# RPI_3.net
KiCad netlist of a schematic drawn in Altium Designer
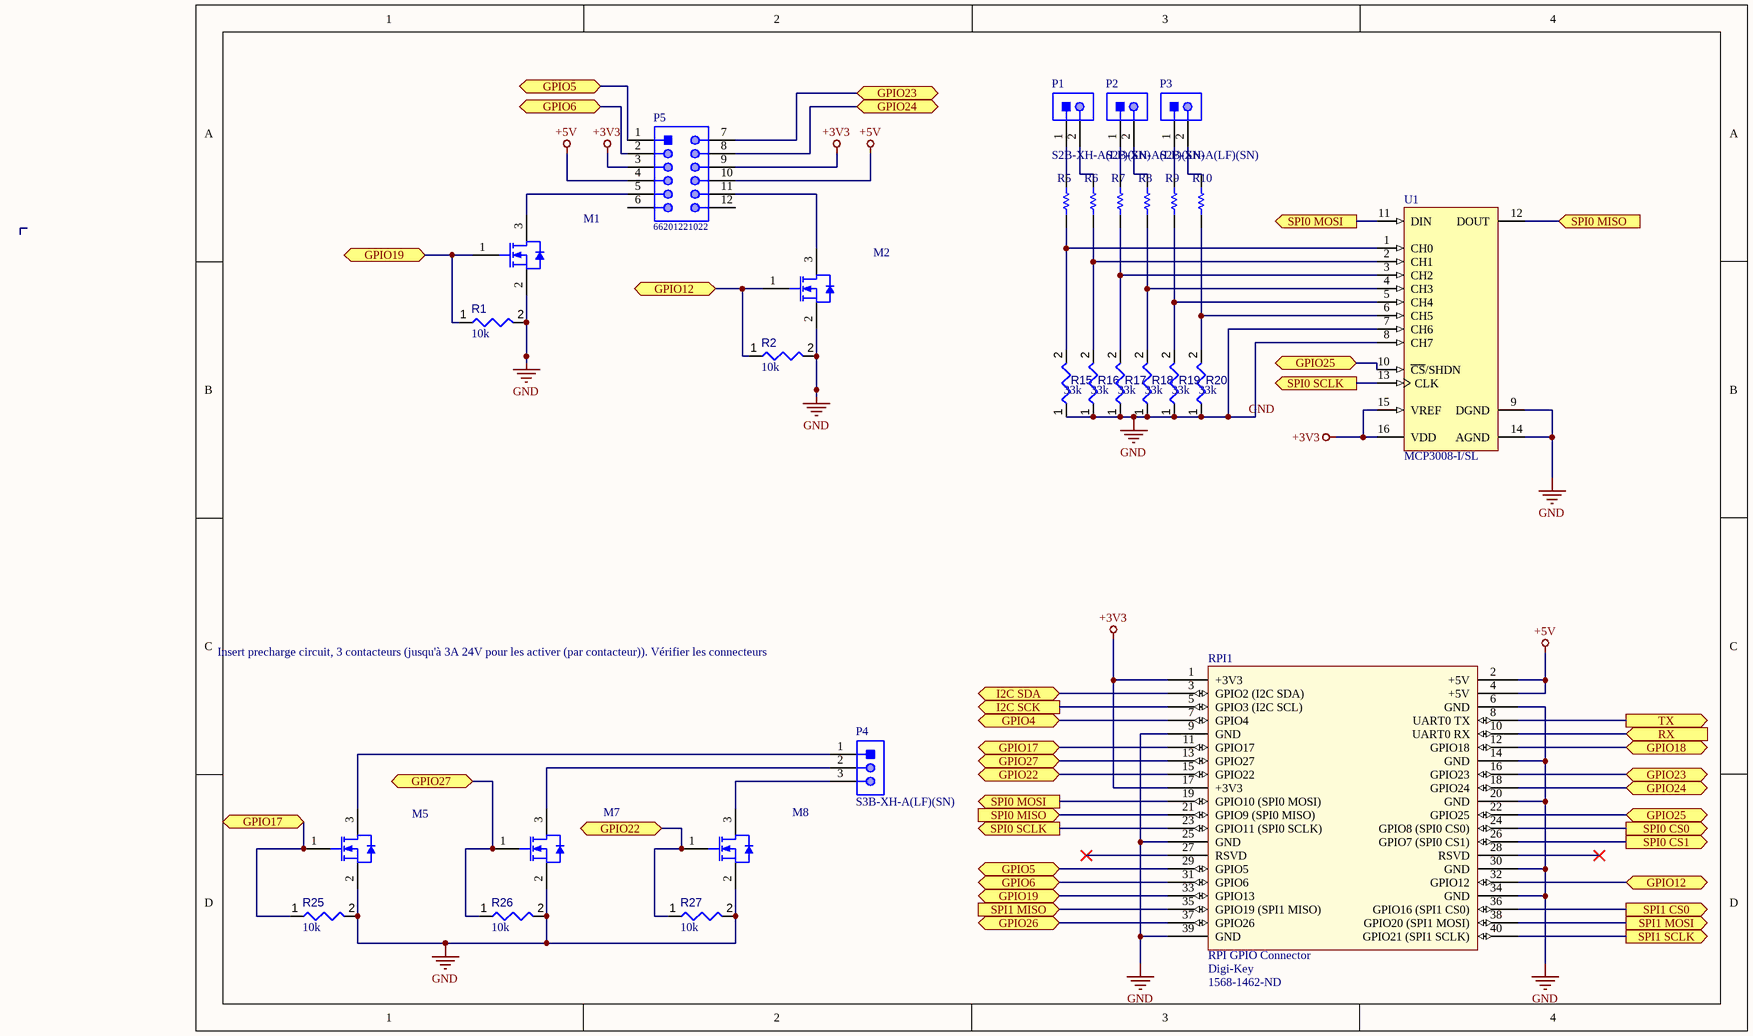
[diagram p0: RPI 3.SchDoc]

(export (version "E")
  (design (tool "Eeschema 10.0.6"))
  (components
    (comp (ref "M1")
      (value "BSS138")
      (footprint "FAIR-SOT23-3_V")
      (fields (field (name "MANUFACTURER") "Fairchild") (field (name "POWER") "360mW"))
      (libsource (lib "École Polytechnique de Montréal") (part "NEMOS-GSD-3"))
    )
    (comp (ref "M2")
      (value "BSS138")
      (footprint "FAIR-SOT23-3_V")
      (fields (field (name "MANUFACTURER") "Fairchild") (field (name "POWER") "360mW"))
      (libsource (lib "École Polytechnique de Montréal") (part "NEMOS-GSD-3"))
    )
    (comp (ref "M5")
      (value "BSS138")
      (footprint "FAIR-SOT23-3_V")
      (fields (field (name "MANUFACTURER") "Fairchild") (field (name "POWER") "360mW"))
      (libsource (lib "École Polytechnique de Montréal") (part "NEMOS-GSD-3"))
    )
    (comp (ref "M7")
      (value "BSS138")
      (footprint "FAIR-SOT23-3_V")
      (fields (field (name "MANUFACTURER") "Fairchild") (field (name "POWER") "360mW"))
      (libsource (lib "École Polytechnique de Montréal") (part "NEMOS-GSD-3"))
    )
    (comp (ref "M8")
      (value "BSS138")
      (footprint "FAIR-SOT23-3_V")
      (fields (field (name "MANUFACTURER") "Fairchild") (field (name "POWER") "360mW"))
      (libsource (lib "École Polytechnique de Montréal") (part "NEMOS-GSD-3"))
    )
    (comp (ref "P1")
      (value "S2B-XH-A(LF)(SN)")
      (footprint "JST-S2B-XH-A(LF)(SN)_V")
      (fields (field (name "MANUFACTURER") "JST"))
      (libsource (lib "École Polytechnique de Montréal") (part "CN-1P-M-R2"))
    )
    (comp (ref "P2")
      (value "S2B-XH-A(LF)(SN)")
      (footprint "JST-S2B-XH-A(LF)(SN)_V")
      (fields (field (name "MANUFACTURER") "JST"))
      (libsource (lib "École Polytechnique de Montréal") (part "CN-1P-M-R2"))
    )
    (comp (ref "P3")
      (value "S2B-XH-A(LF)(SN)")
      (footprint "JST-S2B-XH-A(LF)(SN)_V")
      (fields (field (name "MANUFACTURER") "JST"))
      (libsource (lib "École Polytechnique de Montréal") (part "CN-1P-M-R2"))
    )
    (comp (ref "P4")
      (value "S3B-XH-A(LF)(SN)")
      (footprint "JST-S3B-XH-A(LF)(SN)_V")
      (fields (field (name "MANUFACTURER") "JST"))
      (libsource (lib "École Polytechnique de Montréal") (part "CN-1P-M-R3"))
    )
    (comp (ref "P5")
      (value "66201221022")
      (footprint "66201221022")
      (description "THT Male Header WR-MPC3, with Snap-in Plastic Pegs, Right Angled, Dual Row, pitch 3 mm, 12 pins")
      (libsource (lib "École Polytechnique de Montréal") (part "WE-CN-2P-M-R12_A"))
    )
    (comp (ref "R1")
      (value "10k")
      (footprint "RESC0402(1005)_L")
      (description "Chip Resistor, 10 kOhms, +/-1 %, 63 mW, -55 to 125 degC, 0402")
      (fields (field (name "POWER") "63mW") (field (name "TOLERANCE") "1%"))
      (libsource (lib "École Polytechnique de Montréal") (part "RES-2"))
    )
    (comp (ref "R2")
      (value "10k")
      (footprint "RESC0402(1005)_L")
      (description "Chip Resistor, 10 kOhms, +/-1 %, 63 mW, -55 to 125 degC, 0402")
      (fields (field (name "POWER") "63mW") (field (name "TOLERANCE") "1%"))
      (libsource (lib "École Polytechnique de Montréal") (part "RES-2"))
    )
    (comp (ref "R5")
      (value "RES")
      (footprint "RESC1005X40X25LL05T10")
      (description "Res General Purpose Thick Film 0402 18k Ohm 5% 1/16W ±100ppm/°C Molded Paper T/R")
      (libsource (lib "École Polytechnique de Montréal") (part "RES"))
    )
    (comp (ref "R6")
      (value "RES")
      (footprint "RESC1005X40X25LL05T10")
      (description "Res General Purpose Thick Film 0402 18k Ohm 5% 1/16W ±100ppm/°C Molded Paper T/R")
      (libsource (lib "École Polytechnique de Montréal") (part "RES"))
    )
    (comp (ref "R7")
      (value "RES")
      (footprint "RESC1005X40X25LL05T10")
      (description "Res General Purpose Thick Film 0402 18k Ohm 5% 1/16W ±100ppm/°C Molded Paper T/R")
      (libsource (lib "École Polytechnique de Montréal") (part "RES"))
    )
    (comp (ref "R8")
      (value "RES")
      (footprint "RESC1005X40X25LL05T10")
      (description "Res General Purpose Thick Film 0402 18k Ohm 5% 1/16W ±100ppm/°C Molded Paper T/R")
      (libsource (lib "École Polytechnique de Montréal") (part "RES"))
    )
    (comp (ref "R9")
      (value "RES")
      (footprint "RESC1005X40X25LL05T10")
      (description "Res General Purpose Thick Film 0402 18k Ohm 5% 1/16W ±100ppm/°C Molded Paper T/R")
      (libsource (lib "École Polytechnique de Montréal") (part "RES"))
    )
    (comp (ref "R10")
      (value "RES")
      (footprint "RESC1005X40X25LL05T10")
      (description "Res General Purpose Thick Film 0402 18k Ohm 5% 1/16W ±100ppm/°C Molded Paper T/R")
      (libsource (lib "École Polytechnique de Montréal") (part "RES"))
    )
    (comp (ref "R15")
      (value "33k")
      (footprint "RESC1005X40X25ML10T10")
      (description "Chip Resistor, 33 KOhm, +/- 5%, 0.063 W, -55 to 155 degC, 0402 (1005 Metric)")
      (fields (field (name "TOLERANCE") "5%") (field (name "POWER") "63mW"))
      (libsource (lib "École Polytechnique de Montréal") (part "RES-2"))
    )
    (comp (ref "R16")
      (value "33k")
      (footprint "RESC1005X40X25ML10T10")
      (description "Chip Resistor, 33 KOhm, +/- 5%, 0.063 W, -55 to 155 degC, 0402 (1005 Metric)")
      (fields (field (name "TOLERANCE") "5%") (field (name "POWER") "63mW"))
      (libsource (lib "École Polytechnique de Montréal") (part "RES-2"))
    )
    (comp (ref "R17")
      (value "33k")
      (footprint "RESC1005X40X25ML10T10")
      (description "Chip Resistor, 33 KOhm, +/- 5%, 0.063 W, -55 to 155 degC, 0402 (1005 Metric)")
      (fields (field (name "TOLERANCE") "5%") (field (name "POWER") "63mW"))
      (libsource (lib "École Polytechnique de Montréal") (part "RES-2"))
    )
    (comp (ref "R18")
      (value "33k")
      (footprint "RESC1005X40X25ML10T10")
      (description "Chip Resistor, 33 KOhm, +/- 5%, 0.063 W, -55 to 155 degC, 0402 (1005 Metric)")
      (fields (field (name "TOLERANCE") "5%") (field (name "POWER") "63mW"))
      (libsource (lib "École Polytechnique de Montréal") (part "RES-2"))
    )
    (comp (ref "R19")
      (value "33k")
      (footprint "RESC1005X40X25ML10T10")
      (description "Chip Resistor, 33 KOhm, +/- 5%, 0.063 W, -55 to 155 degC, 0402 (1005 Metric)")
      (fields (field (name "TOLERANCE") "5%") (field (name "POWER") "63mW"))
      (libsource (lib "École Polytechnique de Montréal") (part "RES-2"))
    )
    (comp (ref "R20")
      (value "33k")
      (footprint "RESC1005X40X25ML10T10")
      (description "Chip Resistor, 33 KOhm, +/- 5%, 0.063 W, -55 to 155 degC, 0402 (1005 Metric)")
      (fields (field (name "TOLERANCE") "5%") (field (name "POWER") "63mW"))
      (libsource (lib "École Polytechnique de Montréal") (part "RES-2"))
    )
    (comp (ref "R25")
      (value "10k")
      (footprint "RESC0402(1005)_L")
      (description "Chip Resistor, 10 kOhms, +/-1 %, 63 mW, -55 to 125 degC, 0402")
      (fields (field (name "POWER") "63mW") (field (name "TOLERANCE") "1%"))
      (libsource (lib "École Polytechnique de Montréal") (part "RES-2"))
    )
    (comp (ref "R26")
      (value "10k")
      (footprint "RESC0402(1005)_L")
      (description "Chip Resistor, 10 kOhms, +/-1 %, 63 mW, -55 to 125 degC, 0402")
      (fields (field (name "POWER") "63mW") (field (name "TOLERANCE") "1%"))
      (libsource (lib "École Polytechnique de Montréal") (part "RES-2"))
    )
    (comp (ref "R27")
      (value "10k")
      (footprint "RESC0402(1005)_L")
      (description "Chip Resistor, 10 kOhms, +/-1 %, 63 mW, -55 to 125 degC, 0402")
      (fields (field (name "POWER") "63mW") (field (name "TOLERANCE") "1%"))
      (libsource (lib "École Polytechnique de Montréal") (part "RES-2"))
    )
    (comp (ref "RPI1")
      (value "RPI GPIO Connector")
      (footprint "rpi")
      (description "GPIO Header for Raspberry Pi A+/B+/Pi 2/Pi 3 - 2x20")
      (fields
        (field (name "MANUFACTURER") "SparkFun Electronics")
        (field (name "MANUFACTURER PART NUMBER") "PRT-14017")
        (field (name "SUPPLIER 1") "Digi-Key")
        (field (name "SUPPLIER PART NUMBER 1") "1568-1462-ND")
      )
      (libsource (lib "rpi") (part "rpi connector"))
    )
    (comp (ref "U1")
      (value "MCP3008-I/SL")
      (footprint "SOIC-SL16_L")
      (libsource (lib "Altium Content Vault") (part "CON-ADC-MCP3008-16"))
    )
  )
  (nets
    (net (code "1") (name "+3V3") (class "Default")
      (node (ref "P5") (pin "3") (pinfunction "3_3") (pintype "passive"))
      (node (ref "P5") (pin "9") (pinfunction "9_9") (pintype "passive"))
      (node (ref "RPI1") (pin "1") (pinfunction "+3V3_1") (pintype "power_in"))
      (node (ref "RPI1") (pin "17") (pinfunction "+3V3_17") (pintype "power_in"))
      (node (ref "U1") (pin "15") (pinfunction "VREF_15") (pintype "input"))
      (node (ref "U1") (pin "16") (pinfunction "VDD_16") (pintype "power_in"))
    )
    (net (code "2") (name "+5V") (class "Default")
      (node (ref "P5") (pin "10") (pinfunction "10_10") (pintype "passive"))
      (node (ref "P5") (pin "4") (pinfunction "4_4") (pintype "passive"))
      (node (ref "RPI1") (pin "2") (pinfunction "+5V_2") (pintype "power_in"))
      (node (ref "RPI1") (pin "4") (pinfunction "+5V_4") (pintype "power_in"))
    )
    (net (code "3") (name "/GPIO4") (class "Default")
      (node (ref "RPI1") (pin "7") (pinfunction "GPIO4_7") (pintype "bidirectional"))
    )
    (net (code "4") (name "/GPIO5") (class "Default")
      (node (ref "P5") (pin "1") (pinfunction "1_1") (pintype "passive"))
      (node (ref "RPI1") (pin "29") (pinfunction "GPIO5_29") (pintype "bidirectional"))
    )
    (net (code "5") (name "/GPIO6") (class "Default")
      (node (ref "P5") (pin "2") (pinfunction "2_2") (pintype "passive"))
      (node (ref "RPI1") (pin "31") (pinfunction "GPIO6_31") (pintype "bidirectional"))
    )
    (net (code "6") (name "/GPIO12") (class "Default")
      (node (ref "M2") (pin "1") (pinfunction "G_1") (pintype "passive"))
      (node (ref "R2") (pin "1") (pinfunction "1_1") (pintype "passive"))
      (node (ref "RPI1") (pin "32") (pinfunction "GPIO12_32") (pintype "bidirectional"))
    )
    (net (code "7") (name "/GPIO17") (class "Default")
      (node (ref "M5") (pin "1") (pinfunction "G_1") (pintype "passive"))
      (node (ref "R25") (pin "1") (pinfunction "1_1") (pintype "passive"))
      (node (ref "RPI1") (pin "11") (pinfunction "GPIO17_11") (pintype "bidirectional"))
    )
    (net (code "8") (name "/GPIO18") (class "Default")
      (node (ref "RPI1") (pin "12") (pinfunction "GPIO18_12") (pintype "bidirectional"))
    )
    (net (code "9") (name "/GPIO19") (class "Default")
      (node (ref "M1") (pin "1") (pinfunction "G_1") (pintype "passive"))
      (node (ref "R1") (pin "1") (pinfunction "1_1") (pintype "passive"))
      (node (ref "RPI1") (pin "33") (pinfunction "GPIO13_33") (pintype "bidirectional"))
    )
    (net (code "10") (name "/GPIO22") (class "Default")
      (node (ref "M8") (pin "1") (pinfunction "G_1") (pintype "passive"))
      (node (ref "R27") (pin "1") (pinfunction "1_1") (pintype "passive"))
      (node (ref "RPI1") (pin "15") (pinfunction "GPIO22_15") (pintype "bidirectional"))
    )
    (net (code "11") (name "/GPIO23") (class "Default")
      (node (ref "P5") (pin "7") (pinfunction "7_7") (pintype "passive"))
      (node (ref "RPI1") (pin "16") (pinfunction "GPIO23_16") (pintype "bidirectional"))
    )
    (net (code "12") (name "/GPIO24") (class "Default")
      (node (ref "P5") (pin "8") (pinfunction "8_8") (pintype "passive"))
      (node (ref "RPI1") (pin "18") (pinfunction "GPIO24_18") (pintype "bidirectional"))
    )
    (net (code "13") (name "/GPIO25") (class "Default")
      (node (ref "RPI1") (pin "22") (pinfunction "GPIO25_22") (pintype "bidirectional"))
      (node (ref "U1") (pin "10") (pinfunction "~{CS}/SHDN_10") (pintype "input"))
    )
    (net (code "14") (name "/GPIO26") (class "Default")
      (node (ref "RPI1") (pin "37") (pinfunction "GPIO26_37") (pintype "bidirectional"))
    )
    (net (code "15") (name "/GPIO27") (class "Default")
      (node (ref "M7") (pin "1") (pinfunction "G_1") (pintype "passive"))
      (node (ref "R26") (pin "1") (pinfunction "1_1") (pintype "passive"))
      (node (ref "RPI1") (pin "13") (pinfunction "GPIO27_13") (pintype "bidirectional"))
    )
    (net (code "16") (name "/I2C SCK") (class "Default")
      (node (ref "RPI1") (pin "5") (pinfunction "GPIO3_(I2C_SCL)_5") (pintype "bidirectional"))
    )
    (net (code "17") (name "/I2C SDA") (class "Default")
      (node (ref "RPI1") (pin "3") (pinfunction "GPIO2_(I2C_SDA)_3") (pintype "bidirectional"))
    )
    (net (code "18") (name "/RX") (class "Default")
      (node (ref "RPI1") (pin "10") (pinfunction "UART0_RX_10") (pintype "bidirectional"))
    )
    (net (code "19") (name "/SPI0 CS0") (class "Default")
      (node (ref "RPI1") (pin "24") (pinfunction "GPIO8_(SPI0_CS0)_24") (pintype "bidirectional"))
    )
    (net (code "20") (name "/SPI0 CS1") (class "Default")
      (node (ref "RPI1") (pin "26") (pinfunction "GPIO7_(SPI0_CS1)_26") (pintype "bidirectional"))
    )
    (net (code "21") (name "/SPI0 MISO") (class "Default")
      (node (ref "RPI1") (pin "21") (pinfunction "GPIO9_(SPI0_MISO)_21") (pintype "bidirectional"))
      (node (ref "U1") (pin "12") (pinfunction "DOUT_12") (pintype "tri_state"))
    )
    (net (code "22") (name "/SPI0 MOSI") (class "Default")
      (node (ref "RPI1") (pin "19") (pinfunction "GPIO10_(SPI0_MOSI)_19") (pintype "bidirectional"))
      (node (ref "U1") (pin "11") (pinfunction "DIN_11") (pintype "input"))
    )
    (net (code "23") (name "/SPI0 SCLK") (class "Default")
      (node (ref "RPI1") (pin "23") (pinfunction "GPIO11_(SPI0_SCLK)_23") (pintype "bidirectional"))
      (node (ref "U1") (pin "13") (pinfunction "CLK_13") (pintype "input"))
    )
    (net (code "24") (name "/SPI1 CS0") (class "Default")
      (node (ref "RPI1") (pin "36") (pinfunction "GPIO16_(SPI1_CS0)_36") (pintype "bidirectional"))
    )
    (net (code "25") (name "/SPI1 MISO") (class "Default")
      (node (ref "RPI1") (pin "35") (pinfunction "GPIO19_(SPI1_MISO)_35") (pintype "bidirectional"))
    )
    (net (code "26") (name "/SPI1 MOSI") (class "Default")
      (node (ref "RPI1") (pin "38") (pinfunction "GPIO20_(SPI1_MOSI)_38") (pintype "bidirectional"))
    )
    (net (code "27") (name "/SPI1 SCLK") (class "Default")
      (node (ref "RPI1") (pin "40") (pinfunction "GPIO21_(SPI1_SCLK)_40") (pintype "bidirectional"))
    )
    (net (code "28") (name "/TX") (class "Default")
      (node (ref "RPI1") (pin "8") (pinfunction "UART0_TX_8") (pintype "bidirectional"))
    )
    (net (code "29") (name "GND") (class "Default")
      (node (ref "M1") (pin "2") (pinfunction "S_2") (pintype "passive"))
      (node (ref "M2") (pin "2") (pinfunction "S_2") (pintype "passive"))
      (node (ref "M5") (pin "2") (pinfunction "S_2") (pintype "passive"))
      (node (ref "M7") (pin "2") (pinfunction "S_2") (pintype "passive"))
      (node (ref "M8") (pin "2") (pinfunction "S_2") (pintype "passive"))
      (node (ref "R1") (pin "2") (pinfunction "2_2") (pintype "passive"))
      (node (ref "R15") (pin "1") (pinfunction "1_1") (pintype "passive"))
      (node (ref "R16") (pin "1") (pinfunction "1_1") (pintype "passive"))
      (node (ref "R17") (pin "1") (pinfunction "1_1") (pintype "passive"))
      (node (ref "R18") (pin "1") (pinfunction "1_1") (pintype "passive"))
      (node (ref "R19") (pin "1") (pinfunction "1_1") (pintype "passive"))
      (node (ref "R2") (pin "2") (pinfunction "2_2") (pintype "passive"))
      (node (ref "R20") (pin "1") (pinfunction "1_1") (pintype "passive"))
      (node (ref "R25") (pin "2") (pinfunction "2_2") (pintype "passive"))
      (node (ref "R26") (pin "2") (pinfunction "2_2") (pintype "passive"))
      (node (ref "R27") (pin "2") (pinfunction "2_2") (pintype "passive"))
      (node (ref "RPI1") (pin "14") (pinfunction "GND_14") (pintype "power_in"))
      (node (ref "RPI1") (pin "20") (pinfunction "GND_20") (pintype "power_in"))
      (node (ref "RPI1") (pin "25") (pinfunction "GND_25") (pintype "power_in"))
      (node (ref "RPI1") (pin "30") (pinfunction "GND_30") (pintype "power_in"))
      (node (ref "RPI1") (pin "34") (pinfunction "GND_34") (pintype "passive"))
      (node (ref "RPI1") (pin "39") (pinfunction "GND_39") (pintype "power_in"))
      (node (ref "RPI1") (pin "6") (pinfunction "GND_6") (pintype "power_in"))
      (node (ref "RPI1") (pin "9") (pinfunction "GND_9") (pintype "power_in"))
      (node (ref "U1") (pin "14") (pinfunction "AGND_14") (pintype "power_in"))
      (node (ref "U1") (pin "7") (pinfunction "CH6_7") (pintype "input"))
      (node (ref "U1") (pin "8") (pinfunction "CH7_8") (pintype "input"))
      (node (ref "U1") (pin "9") (pinfunction "DGND_9") (pintype "power_in"))
    )
    (net (code "30") (name "Net-(M1-D)") (class "Default")
      (node (ref "M1") (pin "3") (pinfunction "D_3") (pintype "passive"))
      (node (ref "P5") (pin "5") (pinfunction "5_5") (pintype "passive"))
    )
    (net (code "31") (name "Net-(M2-D)") (class "Default")
      (node (ref "M2") (pin "3") (pinfunction "D_3") (pintype "passive"))
      (node (ref "P5") (pin "11") (pinfunction "11_11") (pintype "passive"))
    )
    (net (code "32") (name "Net-(M5-D)") (class "Default")
      (node (ref "M5") (pin "3") (pinfunction "D_3") (pintype "passive"))
      (node (ref "P4") (pin "1") (pinfunction "1_1") (pintype "passive"))
    )
    (net (code "33") (name "Net-(M7-D)") (class "Default")
      (node (ref "M7") (pin "3") (pinfunction "D_3") (pintype "passive"))
      (node (ref "P4") (pin "2") (pinfunction "2_2") (pintype "passive"))
    )
    (net (code "34") (name "Net-(M8-D)") (class "Default")
      (node (ref "M8") (pin "3") (pinfunction "D_3") (pintype "passive"))
      (node (ref "P4") (pin "3") (pinfunction "3_3") (pintype "passive"))
    )
    (net (code "35") (name "Net-(P1-Pad1)") (class "Default")
      (node (ref "P1") (pin "1") (pinfunction "1_1") (pintype "passive"))
      (node (ref "R5") (pin "2") (pinfunction "2_2") (pintype "passive"))
    )
    (net (code "36") (name "Net-(P1-Pad2)") (class "Default")
      (node (ref "P1") (pin "2") (pinfunction "2_2") (pintype "passive"))
      (node (ref "R6") (pin "2") (pinfunction "2_2") (pintype "passive"))
    )
    (net (code "37") (name "Net-(P2-Pad1)") (class "Default")
      (node (ref "P2") (pin "1") (pinfunction "1_1") (pintype "passive"))
      (node (ref "R7") (pin "2") (pinfunction "2_2") (pintype "passive"))
    )
    (net (code "38") (name "Net-(P2-Pad2)") (class "Default")
      (node (ref "P2") (pin "2") (pinfunction "2_2") (pintype "passive"))
      (node (ref "R8") (pin "2") (pinfunction "2_2") (pintype "passive"))
    )
    (net (code "39") (name "Net-(P3-Pad1)") (class "Default")
      (node (ref "P3") (pin "1") (pinfunction "1_1") (pintype "passive"))
      (node (ref "R9") (pin "2") (pinfunction "2_2") (pintype "passive"))
    )
    (net (code "40") (name "Net-(P3-Pad2)") (class "Default")
      (node (ref "P3") (pin "2") (pinfunction "2_2") (pintype "passive"))
      (node (ref "R10") (pin "2") (pinfunction "2_2") (pintype "passive"))
    )
    (net (code "41") (name "Net-(U1-CH0)") (class "Default")
      (node (ref "R15") (pin "2") (pinfunction "2_2") (pintype "passive"))
      (node (ref "R5") (pin "1") (pinfunction "1_1") (pintype "passive"))
      (node (ref "U1") (pin "1") (pinfunction "CH0_1") (pintype "input"))
    )
    (net (code "42") (name "Net-(U1-CH1)") (class "Default")
      (node (ref "R16") (pin "2") (pinfunction "2_2") (pintype "passive"))
      (node (ref "R6") (pin "1") (pinfunction "1_1") (pintype "passive"))
      (node (ref "U1") (pin "2") (pinfunction "CH1_2") (pintype "input"))
    )
    (net (code "43") (name "Net-(U1-CH2)") (class "Default")
      (node (ref "R17") (pin "2") (pinfunction "2_2") (pintype "passive"))
      (node (ref "R7") (pin "1") (pinfunction "1_1") (pintype "passive"))
      (node (ref "U1") (pin "3") (pinfunction "CH2_3") (pintype "input"))
    )
    (net (code "44") (name "Net-(U1-CH3)") (class "Default")
      (node (ref "R18") (pin "2") (pinfunction "2_2") (pintype "passive"))
      (node (ref "R8") (pin "1") (pinfunction "1_1") (pintype "passive"))
      (node (ref "U1") (pin "4") (pinfunction "CH3_4") (pintype "input"))
    )
    (net (code "45") (name "Net-(U1-CH4)") (class "Default")
      (node (ref "R19") (pin "2") (pinfunction "2_2") (pintype "passive"))
      (node (ref "R9") (pin "1") (pinfunction "1_1") (pintype "passive"))
      (node (ref "U1") (pin "5") (pinfunction "CH4_5") (pintype "input"))
    )
    (net (code "46") (name "Net-(U1-CH5)") (class "Default")
      (node (ref "R10") (pin "1") (pinfunction "1_1") (pintype "passive"))
      (node (ref "R20") (pin "2") (pinfunction "2_2") (pintype "passive"))
      (node (ref "U1") (pin "6") (pinfunction "CH5_6") (pintype "input"))
    )
    (net (code "47") (name "unconnected-(P5-Pad6)") (class "Default")
      (node (ref "P5") (pin "6") (pinfunction "6_6") (pintype "passive"))
    )
    (net (code "48") (name "unconnected-(P5-Pad12)") (class "Default")
      (node (ref "P5") (pin "12") (pinfunction "12_12") (pintype "passive"))
    )
    (net (code "49") (name "unconnected-(RPI1-RSVD-Pad27)") (class "Default")
      (node (ref "RPI1") (pin "27") (pinfunction "RSVD_27") (pintype "passive+no_connect"))
    )
    (net (code "50") (name "unconnected-(RPI1-RSVD-Pad28)") (class "Default")
      (node (ref "RPI1") (pin "28") (pinfunction "RSVD_28") (pintype "passive+no_connect"))
    )
  )
)
